# Main_board_Giulia.net
KiCad netlist of a schematic drawn in EAGLE
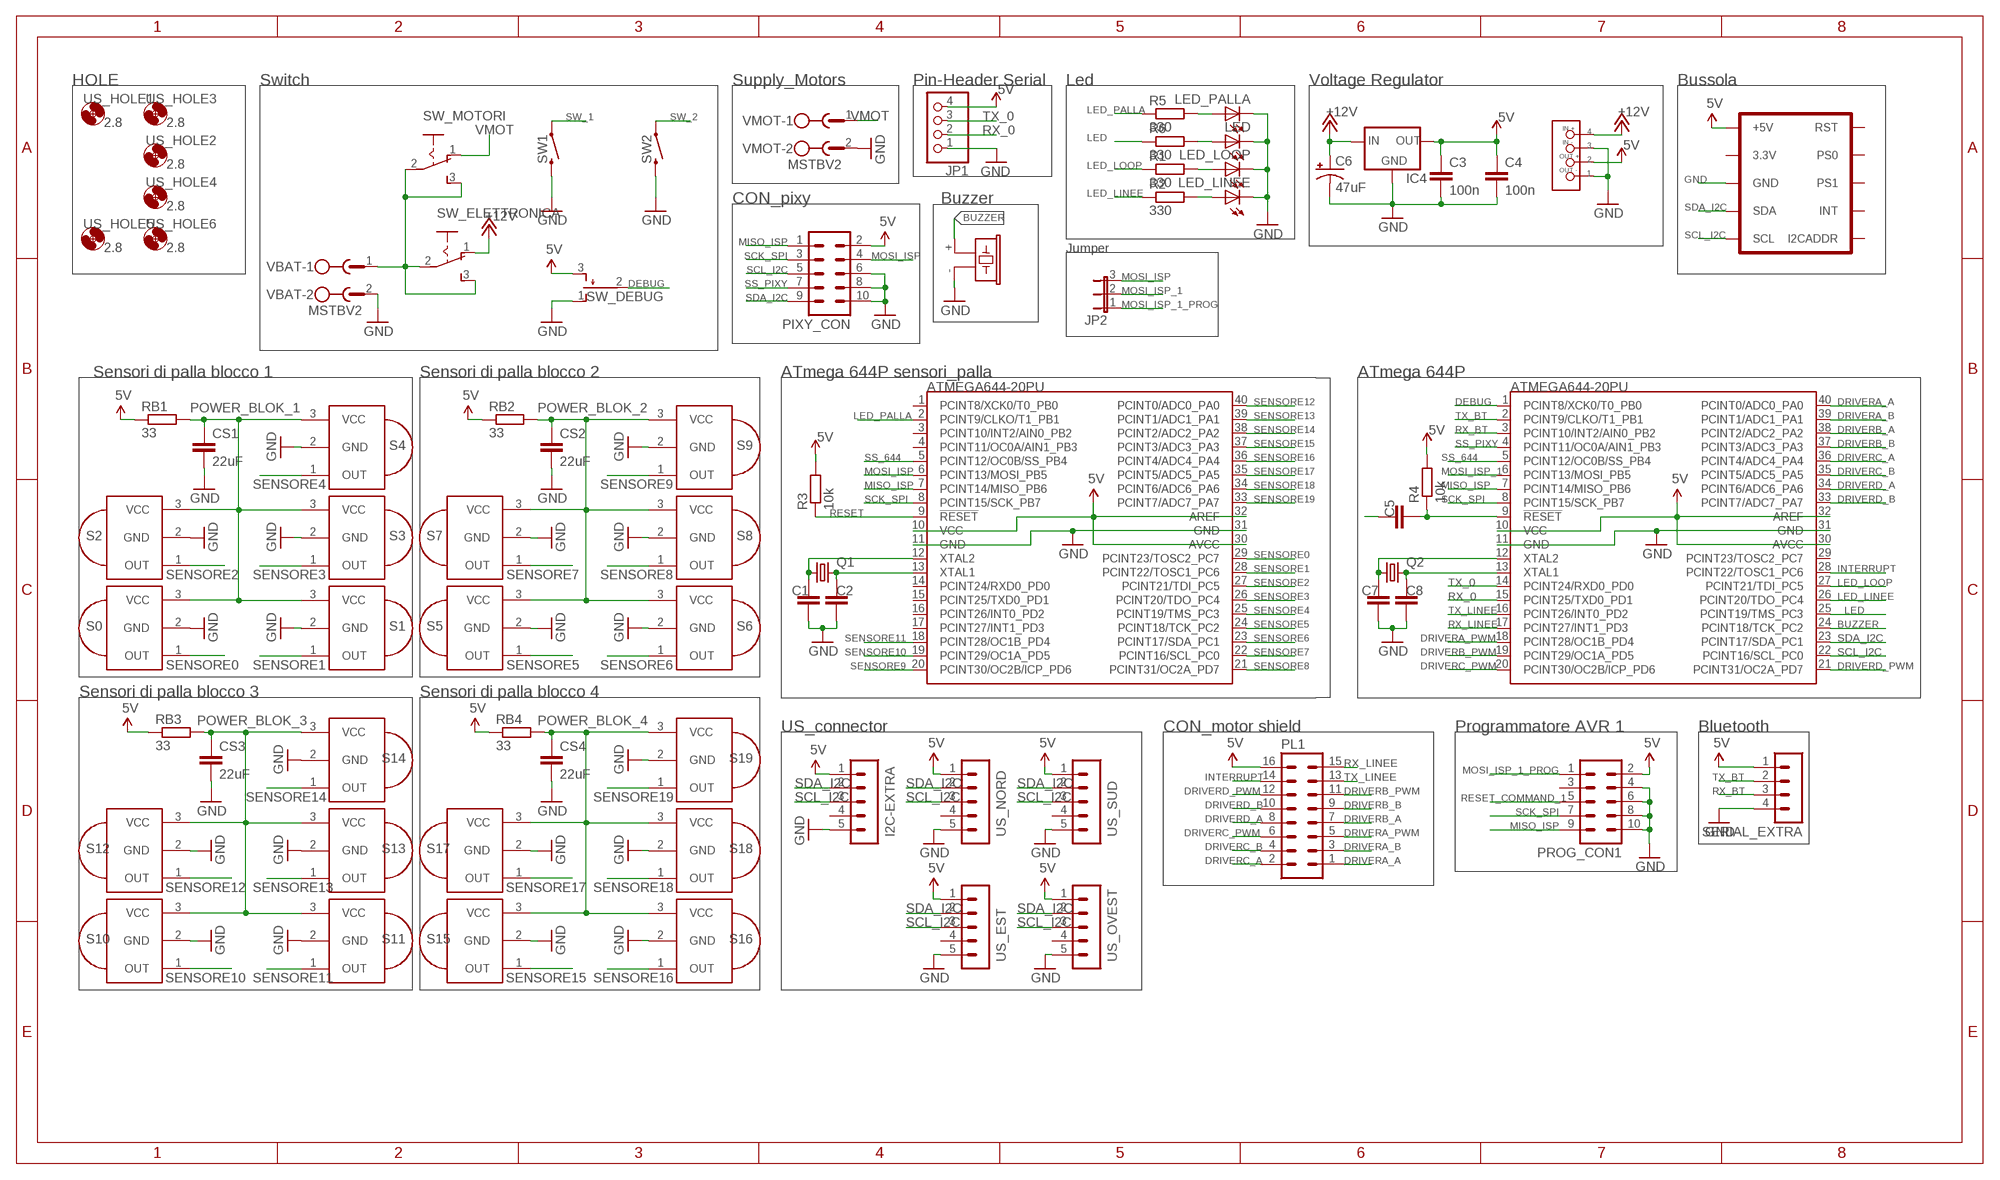
[diagram p0: schematic, sheet 1]

(export (version "E")
  (design (tool "Eeschema 10.0.6"))
  (components
    (comp (ref "C1")
      (value "18p")
      (footprint "eagle-import:C1206")
      (libsource (lib "eagle-import") (part "C-EUC1206"))
    )
    (comp (ref "C2")
      (value "18p")
      (footprint "eagle-import:C1206")
      (libsource (lib "eagle-import") (part "C-EUC1206"))
    )
    (comp (ref "C3")
      (value "100n")
      (footprint "eagle-import:C050-025X075")
      (libsource (lib "eagle-import") (part "C-EU050-025X075"))
    )
    (comp (ref "C4")
      (value "100n")
      (footprint "eagle-import:C050-025X075")
      (libsource (lib "eagle-import") (part "C-EU050-025X075"))
    )
    (comp (ref "C5")
      (value "0.1uF")
      (footprint "eagle-import:C1206")
      (libsource (lib "eagle-import") (part "C-EUC1206"))
    )
    (comp (ref "C6")
      (value "47uF")
      (footprint "eagle-import:CPOL-RADIAL-100UF-25V")
      (libsource (lib "eagle-import") (part "CAP_POLPTH1"))
    )
    (comp (ref "C7")
      (value "18p")
      (footprint "eagle-import:C1206")
      (libsource (lib "eagle-import") (part "C-EUC1206"))
    )
    (comp (ref "C8")
      (value "18p")
      (footprint "eagle-import:C1206")
      (libsource (lib "eagle-import") (part "C-EUC1206"))
    )
    (comp (ref "CS1")
      (value "22uF")
      (footprint "eagle-import:C1206")
      (libsource (lib "eagle-import") (part "C-EUC1206"))
    )
    (comp (ref "CS2")
      (value "22uF")
      (footprint "eagle-import:C1206")
      (libsource (lib "eagle-import") (part "C-EUC1206"))
    )
    (comp (ref "CS3")
      (value "22uF")
      (footprint "eagle-import:C1206")
      (libsource (lib "eagle-import") (part "C-EUC1206"))
    )
    (comp (ref "CS4")
      (value "22uF")
      (footprint "eagle-import:C1206")
      (libsource (lib "eagle-import") (part "C-EUC1206"))
    )
    (comp (ref "I2C-EXTRA")
      (value "MA05-1")
      (footprint "eagle-import:MA05-1")
      (libsource (lib "eagle-import") (part "MA05-1"))
    )
    (comp (ref "IC2")
      (value "ATMEGA644-20PU")
      (footprint "eagle-import:DIL40")
      (libsource (lib "eagle-import") (part "ATMEGA644-PU20"))
    )
    (comp (ref "IC3")
      (value "ATMEGA644-20PU")
      (footprint "eagle-import:DIL40")
      (libsource (lib "eagle-import") (part "ATMEGA644-PU20"))
    )
    (comp (ref "IC4")
      (value "V_REG_78XXSIDE")
      (footprint "eagle-import:78XXL")
      (libsource (lib "eagle-import") (part "V_REG_78XXSIDE"))
    )
    (comp (ref "JP1")
      (value "PINHD-1X4")
      (footprint "eagle-import:1X04")
      (libsource (lib "eagle-import") (part "PINHD-1X4"))
    )
    (comp (ref "JP2")
      (value "JP2E")
      (footprint "eagle-import:JP2")
      (libsource (lib "eagle-import") (part "JP2E"))
    )
    (comp (ref "LED")
      (value "LED3MM")
      (footprint "eagle-import:LED3MM")
      (libsource (lib "eagle-import") (part "LED3MM"))
    )
    (comp (ref "LED_LINEE")
      (value "LED3MM")
      (footprint "eagle-import:LED3MM")
      (libsource (lib "eagle-import") (part "LED3MM"))
    )
    (comp (ref "LED_LOOP")
      (value "LED3MM")
      (footprint "eagle-import:LED3MM")
      (libsource (lib "eagle-import") (part "LED3MM"))
    )
    (comp (ref "LED_PALLA")
      (value "LED3MM")
      (footprint "eagle-import:LED3MM")
      (libsource (lib "eagle-import") (part "LED3MM"))
    )
    (comp (ref "PIXY_CON")
      (value "10V")
      (footprint "eagle-import:10V")
      (libsource (lib "eagle-import") (part "10V"))
    )
    (comp (ref "PL1")
      (value "16V")
      (footprint "eagle-import:16V")
      (libsource (lib "eagle-import") (part "16V"))
    )
    (comp (ref "PROG_CON1")
      (value "10V")
      (footprint "eagle-import:10V")
      (libsource (lib "eagle-import") (part "10V"))
    )
    (comp (ref "Q1")
      (value "CRYSTALHC49UV")
      (footprint "eagle-import:HC49U-V")
      (libsource (lib "eagle-import") (part "CRYSTALHC49UV"))
    )
    (comp (ref "Q2")
      (value "CRYSTALHC49UV")
      (footprint "eagle-import:HC49U-V")
      (libsource (lib "eagle-import") (part "CRYSTALHC49UV"))
    )
    (comp (ref "R1")
      (value "330")
      (footprint "eagle-import:M1206")
      (libsource (lib "eagle-import") (part "R-EU_M1206"))
    )
    (comp (ref "R2")
      (value "330")
      (footprint "eagle-import:M1206")
      (libsource (lib "eagle-import") (part "R-EU_M1206"))
    )
    (comp (ref "R3")
      (value "10k")
      (footprint "eagle-import:M1206")
      (libsource (lib "eagle-import") (part "R-EU_M1206"))
    )
    (comp (ref "R4")
      (value "10k")
      (footprint "eagle-import:M1206")
      (libsource (lib "eagle-import") (part "R-EU_M1206"))
    )
    (comp (ref "R5")
      (value "330")
      (footprint "eagle-import:M1206")
      (libsource (lib "eagle-import") (part "R-EU_M1206"))
    )
    (comp (ref "R6")
      (value "330")
      (footprint "eagle-import:M1206")
      (libsource (lib "eagle-import") (part "R-EU_M1206"))
    )
    (comp (ref "RB1")
      (value "33")
      (footprint "eagle-import:0207_10")
      (libsource (lib "eagle-import") (part "R-EU_0207/10"))
    )
    (comp (ref "RB2")
      (value "33")
      (footprint "eagle-import:0207_10")
      (libsource (lib "eagle-import") (part "R-EU_0207/10"))
    )
    (comp (ref "RB3")
      (value "33")
      (footprint "eagle-import:0207_10")
      (libsource (lib "eagle-import") (part "R-EU_0207/10"))
    )
    (comp (ref "RB4")
      (value "33")
      (footprint "eagle-import:0207_10")
      (libsource (lib "eagle-import") (part "R-EU_0207/10"))
    )
    (comp (ref "S0")
      (value "PNA460XM")
      (footprint "eagle-import:PNA460XM")
      (libsource (lib "eagle-import") (part "PNA460XM"))
    )
    (comp (ref "S1")
      (value "PNA460XM")
      (footprint "eagle-import:PNA460XM")
      (libsource (lib "eagle-import") (part "PNA460XM"))
    )
    (comp (ref "S2")
      (value "PNA460XM")
      (footprint "eagle-import:PNA460XM")
      (libsource (lib "eagle-import") (part "PNA460XM"))
    )
    (comp (ref "S3")
      (value "PNA460XM")
      (footprint "eagle-import:PNA460XM")
      (libsource (lib "eagle-import") (part "PNA460XM"))
    )
    (comp (ref "S4")
      (value "PNA460XM")
      (footprint "eagle-import:PNA460XM")
      (libsource (lib "eagle-import") (part "PNA460XM"))
    )
    (comp (ref "S5")
      (value "PNA460XM")
      (footprint "eagle-import:PNA460XM")
      (libsource (lib "eagle-import") (part "PNA460XM"))
    )
    (comp (ref "S6")
      (value "PNA460XM")
      (footprint "eagle-import:PNA460XM")
      (libsource (lib "eagle-import") (part "PNA460XM"))
    )
    (comp (ref "S7")
      (value "PNA460XM")
      (footprint "eagle-import:PNA460XM")
      (libsource (lib "eagle-import") (part "PNA460XM"))
    )
    (comp (ref "S8")
      (value "PNA460XM")
      (footprint "eagle-import:PNA460XM")
      (libsource (lib "eagle-import") (part "PNA460XM"))
    )
    (comp (ref "S9")
      (value "PNA460XM")
      (footprint "eagle-import:PNA460XM")
      (libsource (lib "eagle-import") (part "PNA460XM"))
    )
    (comp (ref "S10")
      (value "PNA460XM")
      (footprint "eagle-import:PNA460XM")
      (libsource (lib "eagle-import") (part "PNA460XM"))
    )
    (comp (ref "S11")
      (value "PNA460XM")
      (footprint "eagle-import:PNA460XM")
      (libsource (lib "eagle-import") (part "PNA460XM"))
    )
    (comp (ref "S12")
      (value "PNA460XM")
      (footprint "eagle-import:PNA460XM")
      (libsource (lib "eagle-import") (part "PNA460XM"))
    )
    (comp (ref "S13")
      (value "PNA460XM")
      (footprint "eagle-import:PNA460XM")
      (libsource (lib "eagle-import") (part "PNA460XM"))
    )
    (comp (ref "S14")
      (value "PNA460XM")
      (footprint "eagle-import:PNA460XM")
      (libsource (lib "eagle-import") (part "PNA460XM"))
    )
    (comp (ref "S15")
      (value "PNA460XM")
      (footprint "eagle-import:PNA460XM")
      (libsource (lib "eagle-import") (part "PNA460XM"))
    )
    (comp (ref "S16")
      (value "PNA460XM")
      (footprint "eagle-import:PNA460XM")
      (libsource (lib "eagle-import") (part "PNA460XM"))
    )
    (comp (ref "S17")
      (value "PNA460XM")
      (footprint "eagle-import:PNA460XM")
      (libsource (lib "eagle-import") (part "PNA460XM"))
    )
    (comp (ref "S18")
      (value "PNA460XM")
      (footprint "eagle-import:PNA460XM")
      (libsource (lib "eagle-import") (part "PNA460XM"))
    )
    (comp (ref "S19")
      (value "PNA460XM")
      (footprint "eagle-import:PNA460XM")
      (libsource (lib "eagle-import") (part "PNA460XM"))
    )
    (comp (ref "SERIAL_EXTRA")
      (value "MA04-1")
      (footprint "eagle-import:MA04-1")
      (libsource (lib "eagle-import") (part "MA04-1"))
    )
    (comp (ref "SG1")
      (value "F/CM12P")
      (footprint "eagle-import:F_CM12P")
      (libsource (lib "eagle-import") (part "F/CM12P"))
    )
    (comp (ref "SW1")
      (value "SWITCH-MOMENTARY-2")
      (footprint "eagle-import:SWITCH_EVQ2")
      (libsource (lib "eagle-import") (part "SWITCH-MOMENTARY-2"))
    )
    (comp (ref "SW2")
      (value "SWITCH-MOMENTARY-2")
      (footprint "eagle-import:SWITCH_EVQ2")
      (libsource (lib "eagle-import") (part "SWITCH-MOMENTARY-2"))
    )
    (comp (ref "SW_DEBUG")
      (value "TL38PO")
      (footprint "eagle-import:TL3XPO")
      (libsource (lib "eagle-import") (part "TL38PO"))
    )
    (comp (ref "SW_ELETTRONICA")
      (value "255SB")
      (footprint "eagle-import:255SB")
      (libsource (lib "eagle-import") (part "255SB"))
    )
    (comp (ref "SW_MOTORI")
      (value "255SB")
      (footprint "eagle-import:255SB")
      (libsource (lib "eagle-import") (part "255SB"))
    )
    (comp (ref "U$1")
      (value "MINI3ADCDCLM2596")
      (footprint "eagle-import:MINI3ADCDCLM2595")
      (libsource (lib "eagle-import") (part "MINI3ADCDCLM2596"))
    )
    (comp (ref "U$17")
      (value "BNO055")
      (footprint "eagle-import:BNO055")
      (libsource (lib "eagle-import") (part "BNO055"))
    )
    (comp (ref "US_EST")
      (value "MA05-1")
      (footprint "eagle-import:MA05-1")
      (libsource (lib "eagle-import") (part "MA05-1"))
    )
    (comp (ref "US_HOLE1")
      (value "2.8")
      (footprint "eagle-import:2,8")
      (libsource (lib "eagle-import") (part "MOUNT-HOLE2.8"))
    )
    (comp (ref "US_HOLE2")
      (value "2.8")
      (footprint "eagle-import:2,8")
      (libsource (lib "eagle-import") (part "MOUNT-HOLE2.8"))
    )
    (comp (ref "US_HOLE3")
      (value "2.8")
      (footprint "eagle-import:2,8")
      (libsource (lib "eagle-import") (part "MOUNT-HOLE2.8"))
    )
    (comp (ref "US_HOLE4")
      (value "2.8")
      (footprint "eagle-import:2,8")
      (libsource (lib "eagle-import") (part "MOUNT-HOLE2.8"))
    )
    (comp (ref "US_HOLE5")
      (value "2.8")
      (footprint "eagle-import:2,8")
      (libsource (lib "eagle-import") (part "MOUNT-HOLE2.8"))
    )
    (comp (ref "US_HOLE6")
      (value "2.8")
      (footprint "eagle-import:2,8")
      (libsource (lib "eagle-import") (part "MOUNT-HOLE2.8"))
    )
    (comp (ref "US_NORD")
      (value "MA05-1")
      (footprint "eagle-import:MA05-1")
      (libsource (lib "eagle-import") (part "MA05-1"))
    )
    (comp (ref "US_OVEST")
      (value "MA05-1")
      (footprint "eagle-import:MA05-1")
      (libsource (lib "eagle-import") (part "MA05-1"))
    )
    (comp (ref "US_SUD")
      (value "MA05-1")
      (footprint "eagle-import:MA05-1")
      (libsource (lib "eagle-import") (part "MA05-1"))
    )
    (comp (ref "VBAT")
      (value "MSTBV2")
      (footprint "eagle-import:MSTBV2")
      (fields (field (name "MPN") "MSTBV 2,5/2-GF-5.08"))
      (libsource (lib "eagle-import") (part "MSTBV2"))
    )
    (comp (ref "VMOT")
      (value "MSTBV2")
      (footprint "eagle-import:MSTBV2")
      (fields (field (name "MPN") "MSTBV 2,5/2-GF-5.08"))
      (libsource (lib "eagle-import") (part "MSTBV2"))
    )
  )
  (nets
    (net (code "1") (name "+12V") (class "Default")
      (node (ref "C6") (pin "1") (pinfunction "+_1") (pintype "passive"))
      (node (ref "IC4") (pin "IN") (pinfunction "IN_IN") (pintype "input"))
      (node (ref "SW_ELETTRONICA") (pin "1") (pinfunction "O_1") (pintype "passive"))
      (node (ref "U$1") (pin "P$2") (pinfunction "IN1_P$2") (pintype "input"))
      (node (ref "U$1") (pin "P$7") (pinfunction "IN1_P$7") (pintype "input"))
    )
    (net (code "2") (name "/DEBUG") (class "Default")
      (node (ref "IC3") (pin "1") (pinfunction "PCINT8/XCK0/T0_PB0_1") (pintype "bidirectional"))
      (node (ref "SW_DEBUG") (pin "2") (pinfunction "P_2") (pintype "passive"))
    )
    (net (code "3") (name "/DRIVERA_A") (class "Default")
      (node (ref "IC3") (pin "40") (pinfunction "PCINT0/ADC0_PA0_40") (pintype "bidirectional"))
      (node (ref "PL1") (pin "1") (pinfunction "1_1") (pintype "passive"))
    )
    (net (code "4") (name "/DRIVERA_B") (class "Default")
      (node (ref "IC3") (pin "39") (pinfunction "PCINT1/ADC1_PA1_39") (pintype "bidirectional"))
      (node (ref "PL1") (pin "3") (pinfunction "3_3") (pintype "passive"))
    )
    (net (code "5") (name "/DRIVERA_PWM") (class "Default")
      (node (ref "IC3") (pin "18") (pinfunction "PCINT28/OC1B_PD4_18") (pintype "bidirectional"))
      (node (ref "PL1") (pin "5") (pinfunction "5_5") (pintype "passive"))
    )
    (net (code "6") (name "/DRIVERB_A") (class "Default")
      (node (ref "IC3") (pin "38") (pinfunction "PCINT2/ADC2_PA2_38") (pintype "bidirectional"))
      (node (ref "PL1") (pin "7") (pinfunction "7_7") (pintype "passive"))
    )
    (net (code "7") (name "/DRIVERB_B") (class "Default")
      (node (ref "IC3") (pin "37") (pinfunction "PCINT3/ADC3_PA3_37") (pintype "bidirectional"))
      (node (ref "PL1") (pin "9") (pinfunction "9_9") (pintype "passive"))
    )
    (net (code "8") (name "/DRIVERB_PWM") (class "Default")
      (node (ref "IC3") (pin "19") (pinfunction "PCINT29/OC1A_PD5_19") (pintype "bidirectional"))
      (node (ref "PL1") (pin "11") (pinfunction "11_11") (pintype "passive"))
    )
    (net (code "9") (name "/DRIVERC_A") (class "Default")
      (node (ref "IC3") (pin "36") (pinfunction "PCINT4/ADC4_PA4_36") (pintype "bidirectional"))
      (node (ref "PL1") (pin "2") (pinfunction "2_2") (pintype "passive"))
    )
    (net (code "10") (name "/DRIVERC_B") (class "Default")
      (node (ref "IC3") (pin "35") (pinfunction "PCINT5/ADC5_PA5_35") (pintype "bidirectional"))
      (node (ref "PL1") (pin "4") (pinfunction "4_4") (pintype "passive"))
    )
    (net (code "11") (name "/DRIVERC_PWM") (class "Default")
      (node (ref "IC3") (pin "20") (pinfunction "PCINT30/OC2B/ICP_PD6_20") (pintype "bidirectional"))
      (node (ref "PL1") (pin "6") (pinfunction "6_6") (pintype "passive"))
    )
    (net (code "12") (name "/DRIVERD_A") (class "Default")
      (node (ref "IC3") (pin "34") (pinfunction "PCINT6/ADC6_PA6_34") (pintype "bidirectional"))
      (node (ref "PL1") (pin "8") (pinfunction "8_8") (pintype "passive"))
    )
    (net (code "13") (name "/DRIVERD_B") (class "Default")
      (node (ref "IC3") (pin "33") (pinfunction "PCINT7/ADC7_PA7_33") (pintype "bidirectional"))
      (node (ref "PL1") (pin "10") (pinfunction "10_10") (pintype "passive"))
    )
    (net (code "14") (name "/DRIVERD_PWM") (class "Default")
      (node (ref "IC3") (pin "21") (pinfunction "PCINT31/OC2A_PD7_21") (pintype "bidirectional"))
      (node (ref "PL1") (pin "12") (pinfunction "12_12") (pintype "passive"))
    )
    (net (code "15") (name "/INTERRUPT") (class "Default")
      (node (ref "IC3") (pin "28") (pinfunction "PCINT22/TOSC1_PC6_28") (pintype "bidirectional"))
      (node (ref "PL1") (pin "14") (pinfunction "14_14") (pintype "passive"))
    )
    (net (code "16") (name "/LED") (class "Default")
      (node (ref "IC3") (pin "25") (pinfunction "PCINT19/TMS_PC3_25") (pintype "bidirectional"))
      (node (ref "R6") (pin "1") (pinfunction "1_1") (pintype "passive"))
    )
    (net (code "17") (name "/LED_LINEE") (class "Default")
      (node (ref "IC3") (pin "26") (pinfunction "PCINT20/TDO_PC4_26") (pintype "bidirectional"))
      (node (ref "R2") (pin "1") (pinfunction "1_1") (pintype "passive"))
    )
    (net (code "18") (name "/LED_LOOP") (class "Default")
      (node (ref "IC3") (pin "27") (pinfunction "PCINT21/TDI_PC5_27") (pintype "bidirectional"))
      (node (ref "R1") (pin "1") (pinfunction "1_1") (pintype "passive"))
    )
    (net (code "19") (name "/LED_PALLA") (class "Default")
      (node (ref "IC2") (pin "2") (pinfunction "PCINT9/CLKO/T1_PB1_2") (pintype "bidirectional"))
      (node (ref "R5") (pin "1") (pinfunction "1_1") (pintype "passive"))
    )
    (net (code "20") (name "/MISO_ISP") (class "Default")
      (node (ref "IC2") (pin "7") (pinfunction "PCINT14/MISO_PB6_7") (pintype "bidirectional"))
      (node (ref "IC3") (pin "7") (pinfunction "PCINT14/MISO_PB6_7") (pintype "bidirectional"))
      (node (ref "PIXY_CON") (pin "1") (pinfunction "1_1") (pintype "passive"))
      (node (ref "PROG_CON1") (pin "9") (pinfunction "9_9") (pintype "passive"))
    )
    (net (code "21") (name "/MOSI_ISP") (class "Default")
      (node (ref "IC2") (pin "6") (pinfunction "PCINT13/MOSI_PB5_6") (pintype "bidirectional"))
      (node (ref "JP2") (pin "3") (pinfunction "3_3") (pintype "passive"))
      (node (ref "PIXY_CON") (pin "4") (pinfunction "4_4") (pintype "passive"))
    )
    (net (code "22") (name "/MOSI_ISP_1") (class "Default")
      (node (ref "IC3") (pin "6") (pinfunction "PCINT13/MOSI_PB5_6") (pintype "bidirectional"))
      (node (ref "JP2") (pin "2") (pinfunction "2_2") (pintype "passive"))
    )
    (net (code "23") (name "/MOSI_ISP_1_PROG") (class "Default")
      (node (ref "JP2") (pin "1") (pinfunction "1_1") (pintype "passive"))
      (node (ref "PROG_CON1") (pin "1") (pinfunction "1_1") (pintype "passive"))
    )
    (net (code "24") (name "/POWER_BLOK_1") (class "Default")
      (node (ref "CS1") (pin "1") (pinfunction "1_1") (pintype "passive"))
      (node (ref "RB1") (pin "2") (pinfunction "2_2") (pintype "passive"))
      (node (ref "S0") (pin "3") (pinfunction "VCC_3") (pintype "power_in"))
      (node (ref "S1") (pin "3") (pinfunction "VCC_3") (pintype "power_in"))
      (node (ref "S2") (pin "3") (pinfunction "VCC_3") (pintype "power_in"))
      (node (ref "S3") (pin "3") (pinfunction "VCC_3") (pintype "power_in"))
      (node (ref "S4") (pin "3") (pinfunction "VCC_3") (pintype "power_in"))
    )
    (net (code "25") (name "/POWER_BLOK_2") (class "Default")
      (node (ref "CS2") (pin "1") (pinfunction "1_1") (pintype "passive"))
      (node (ref "RB2") (pin "2") (pinfunction "2_2") (pintype "passive"))
      (node (ref "S5") (pin "3") (pinfunction "VCC_3") (pintype "power_in"))
      (node (ref "S6") (pin "3") (pinfunction "VCC_3") (pintype "power_in"))
      (node (ref "S7") (pin "3") (pinfunction "VCC_3") (pintype "power_in"))
      (node (ref "S8") (pin "3") (pinfunction "VCC_3") (pintype "power_in"))
      (node (ref "S9") (pin "3") (pinfunction "VCC_3") (pintype "power_in"))
    )
    (net (code "26") (name "/POWER_BLOK_3") (class "Default")
      (node (ref "CS3") (pin "1") (pinfunction "1_1") (pintype "passive"))
      (node (ref "RB3") (pin "2") (pinfunction "2_2") (pintype "passive"))
      (node (ref "S10") (pin "3") (pinfunction "VCC_3") (pintype "power_in"))
      (node (ref "S11") (pin "3") (pinfunction "VCC_3") (pintype "power_in"))
      (node (ref "S12") (pin "3") (pinfunction "VCC_3") (pintype "power_in"))
      (node (ref "S13") (pin "3") (pinfunction "VCC_3") (pintype "power_in"))
      (node (ref "S14") (pin "3") (pinfunction "VCC_3") (pintype "power_in"))
    )
    (net (code "27") (name "/POWER_BLOK_4") (class "Default")
      (node (ref "CS4") (pin "1") (pinfunction "1_1") (pintype "passive"))
      (node (ref "RB4") (pin "2") (pinfunction "2_2") (pintype "passive"))
      (node (ref "S15") (pin "3") (pinfunction "VCC_3") (pintype "power_in"))
      (node (ref "S16") (pin "3") (pinfunction "VCC_3") (pintype "power_in"))
      (node (ref "S17") (pin "3") (pinfunction "VCC_3") (pintype "power_in"))
      (node (ref "S18") (pin "3") (pinfunction "VCC_3") (pintype "power_in"))
      (node (ref "S19") (pin "3") (pinfunction "VCC_3") (pintype "power_in"))
    )
    (net (code "28") (name "/RESET") (class "Default")
      (node (ref "IC2") (pin "9") (pinfunction "~{RESET}_9") (pintype "input"))
      (node (ref "R3") (pin "1") (pinfunction "1_1") (pintype "passive"))
    )
    (net (code "29") (name "/RESET_COMMAND_1") (class "Default")
      (node (ref "C5") (pin "1") (pinfunction "1_1") (pintype "passive"))
      (node (ref "PROG_CON1") (pin "5") (pinfunction "5_5") (pintype "passive"))
    )
    (net (code "30") (name "/RX_0") (class "Default")
      (node (ref "IC3") (pin "15") (pinfunction "PCINT25/TXD0_PD1_15") (pintype "bidirectional"))
      (node (ref "JP1") (pin "2") (pinfunction "2_2") (pintype "passive"))
    )
    (net (code "31") (name "/RX_BT") (class "Default")
      (node (ref "IC3") (pin "3") (pinfunction "PCINT10/INT2/AIN0_PB2_3") (pintype "bidirectional"))
      (node (ref "SERIAL_EXTRA") (pin "3") (pinfunction "3_3") (pintype "passive"))
    )
    (net (code "32") (name "/RX_LINEE") (class "Default")
      (node (ref "IC3") (pin "17") (pinfunction "PCINT27/INT1_PD3_17") (pintype "bidirectional"))
      (node (ref "PL1") (pin "15") (pinfunction "15_15") (pintype "passive"))
    )
    (net (code "33") (name "/SCK_SPI") (class "Default")
      (node (ref "IC2") (pin "8") (pinfunction "PCINT15/SCK_PB7_8") (pintype "bidirectional"))
      (node (ref "IC3") (pin "8") (pinfunction "PCINT15/SCK_PB7_8") (pintype "bidirectional"))
      (node (ref "PIXY_CON") (pin "3") (pinfunction "3_3") (pintype "passive"))
      (node (ref "PROG_CON1") (pin "7") (pinfunction "7_7") (pintype "passive"))
    )
    (net (code "34") (name "/SCL_I2C") (class "Default")
      (node (ref "I2C-EXTRA") (pin "3") (pinfunction "3_3") (pintype "passive"))
      (node (ref "IC3") (pin "22") (pinfunction "PCINT16/SCL_PC0_22") (pintype "bidirectional"))
      (node (ref "PIXY_CON") (pin "5") (pinfunction "5_5") (pintype "passive"))
      (node (ref "U$17") (pin "SCL") (pinfunction "SCL_SCL") (pintype "bidirectional"))
      (node (ref "US_EST") (pin "3") (pinfunction "3_3") (pintype "passive"))
      (node (ref "US_NORD") (pin "3") (pinfunction "3_3") (pintype "passive"))
      (node (ref "US_OVEST") (pin "3") (pinfunction "3_3") (pintype "passive"))
      (node (ref "US_SUD") (pin "3") (pinfunction "3_3") (pintype "passive"))
    )
    (net (code "35") (name "/SDA_I2C") (class "Default")
      (node (ref "I2C-EXTRA") (pin "2") (pinfunction "2_2") (pintype "passive"))
      (node (ref "IC3") (pin "23") (pinfunction "PCINT17/SDA_PC1_23") (pintype "bidirectional"))
      (node (ref "PIXY_CON") (pin "9") (pinfunction "9_9") (pintype "passive"))
      (node (ref "U$17") (pin "SDA") (pinfunction "SDA_SDA") (pintype "bidirectional"))
      (node (ref "US_EST") (pin "2") (pinfunction "2_2") (pintype "passive"))
      (node (ref "US_NORD") (pin "2") (pinfunction "2_2") (pintype "passive"))
      (node (ref "US_OVEST") (pin "2") (pinfunction "2_2") (pintype "passive"))
      (node (ref "US_SUD") (pin "2") (pinfunction "2_2") (pintype "passive"))
    )
    (net (code "36") (name "/SENSORE0") (class "Default")
      (node (ref "IC2") (pin "29") (pinfunction "PCINT23/TOSC2_PC7_29") (pintype "bidirectional"))
      (node (ref "S0") (pin "1") (pinfunction "OUT_1") (pintype "output"))
    )
    (net (code "37") (name "/SENSORE1") (class "Default")
      (node (ref "IC2") (pin "28") (pinfunction "PCINT22/TOSC1_PC6_28") (pintype "bidirectional"))
      (node (ref "S1") (pin "1") (pinfunction "OUT_1") (pintype "output"))
    )
    (net (code "38") (name "/SENSORE2") (class "Default")
      (node (ref "IC2") (pin "27") (pinfunction "PCINT21/TDI_PC5_27") (pintype "bidirectional"))
      (node (ref "S2") (pin "1") (pinfunction "OUT_1") (pintype "output"))
    )
    (net (code "39") (name "/SENSORE3") (class "Default")
      (node (ref "IC2") (pin "26") (pinfunction "PCINT20/TDO_PC4_26") (pintype "bidirectional"))
      (node (ref "S3") (pin "1") (pinfunction "OUT_1") (pintype "output"))
    )
    (net (code "40") (name "/SENSORE4") (class "Default")
      (node (ref "IC2") (pin "25") (pinfunction "PCINT19/TMS_PC3_25") (pintype "bidirectional"))
      (node (ref "S4") (pin "1") (pinfunction "OUT_1") (pintype "output"))
    )
    (net (code "41") (name "/SENSORE5") (class "Default")
      (node (ref "IC2") (pin "24") (pinfunction "PCINT18/TCK_PC2_24") (pintype "bidirectional"))
      (node (ref "S5") (pin "1") (pinfunction "OUT_1") (pintype "output"))
    )
    (net (code "42") (name "/SENSORE6") (class "Default")
      (node (ref "IC2") (pin "23") (pinfunction "PCINT17/SDA_PC1_23") (pintype "bidirectional"))
      (node (ref "S6") (pin "1") (pinfunction "OUT_1") (pintype "output"))
    )
    (net (code "43") (name "/SENSORE7") (class "Default")
      (node (ref "IC2") (pin "22") (pinfunction "PCINT16/SCL_PC0_22") (pintype "bidirectional"))
      (node (ref "S7") (pin "1") (pinfunction "OUT_1") (pintype "output"))
    )
    (net (code "44") (name "/SENSORE8") (class "Default")
      (node (ref "IC2") (pin "21") (pinfunction "PCINT31/OC2A_PD7_21") (pintype "bidirectional"))
      (node (ref "S8") (pin "1") (pinfunction "OUT_1") (pintype "output"))
    )
    (net (code "45") (name "/SENSORE9") (class "Default")
      (node (ref "IC2") (pin "20") (pinfunction "PCINT30/OC2B/ICP_PD6_20") (pintype "bidirectional"))
      (node (ref "S9") (pin "1") (pinfunction "OUT_1") (pintype "output"))
    )
    (net (code "46") (name "/SENSORE10") (class "Default")
      (node (ref "IC2") (pin "19") (pinfunction "PCINT29/OC1A_PD5_19") (pintype "bidirectional"))
      (node (ref "S10") (pin "1") (pinfunction "OUT_1") (pintype "output"))
    )
    (net (code "47") (name "/SENSORE11") (class "Default")
      (node (ref "IC2") (pin "18") (pinfunction "PCINT28/OC1B_PD4_18") (pintype "bidirectional"))
      (node (ref "S11") (pin "1") (pinfunction "OUT_1") (pintype "output"))
    )
    (net (code "48") (name "/SENSORE12") (class "Default")
      (node (ref "IC2") (pin "40") (pinfunction "PCINT0/ADC0_PA0_40") (pintype "bidirectional"))
      (node (ref "S12") (pin "1") (pinfunction "OUT_1") (pintype "output"))
    )
    (net (code "49") (name "/SENSORE13") (class "Default")
      (node (ref "IC2") (pin "39") (pinfunction "PCINT1/ADC1_PA1_39") (pintype "bidirectional"))
      (node (ref "S13") (pin "1") (pinfunction "OUT_1") (pintype "output"))
    )
    (net (code "50") (name "/SENSORE14") (class "Default")
      (node (ref "IC2") (pin "38") (pinfunction "PCINT2/ADC2_PA2_38") (pintype "bidirectional"))
      (node (ref "S14") (pin "1") (pinfunction "OUT_1") (pintype "output"))
    )
    (net (code "51") (name "/SENSORE15") (class "Default")
      (node (ref "IC2") (pin "37") (pinfunction "PCINT3/ADC3_PA3_37") (pintype "bidirectional"))
      (node (ref "S15") (pin "1") (pinfunction "OUT_1") (pintype "output"))
    )
    (net (code "52") (name "/SENSORE16") (class "Default")
      (node (ref "IC2") (pin "36") (pinfunction "PCINT4/ADC4_PA4_36") (pintype "bidirectional"))
      (node (ref "S16") (pin "1") (pinfunction "OUT_1") (pintype "output"))
    )
    (net (code "53") (name "/SENSORE17") (class "Default")
      (node (ref "IC2") (pin "35") (pinfunction "PCINT5/ADC5_PA5_35") (pintype "bidirectional"))
      (node (ref "S17") (pin "1") (pinfunction "OUT_1") (pintype "output"))
    )
    (net (code "54") (name "/SENSORE18") (class "Default")
      (node (ref "IC2") (pin "34") (pinfunction "PCINT6/ADC6_PA6_34") (pintype "bidirectional"))
      (node (ref "S18") (pin "1") (pinfunction "OUT_1") (pintype "output"))
    )
    (net (code "55") (name "/SENSORE19") (class "Default")
      (node (ref "IC2") (pin "33") (pinfunction "PCINT7/ADC7_PA7_33") (pintype "bidirectional"))
      (node (ref "S19") (pin "1") (pinfunction "OUT_1") (pintype "output"))
    )
    (net (code "56") (name "/SS_644") (class "Default")
      (node (ref "IC2") (pin "5") (pinfunction "PCINT12/OC0B/SS_PB4_5") (pintype "bidirectional"))
      (node (ref "IC3") (pin "5") (pinfunction "PCINT12/OC0B/SS_PB4_5") (pintype "bidirectional"))
    )
    (net (code "57") (name "/SS_PIXY") (class "Default")
      (node (ref "IC3") (pin "4") (pinfunction "PCINT11/OC0A/AIN1_PB3_4") (pintype "bidirectional"))
      (node (ref "PIXY_CON") (pin "7") (pinfunction "7_7") (pintype "passive"))
    )
    (net (code "58") (name "/SW_1") (class "Default")
      (node (ref "SW1") (pin "P$1") (pinfunction "1_P$1") (pintype "passive"))
    )
    (net (code "59") (name "/SW_2") (class "Default")
      (node (ref "SW2") (pin "P$1") (pinfunction "1_P$1") (pintype "passive"))
    )
    (net (code "60") (name "/TX_0") (class "Default")
      (node (ref "IC3") (pin "14") (pinfunction "PCINT24/RXD0_PD0_14") (pintype "bidirectional"))
      (node (ref "JP1") (pin "3") (pinfunction "3_3") (pintype "passive"))
    )
    (net (code "61") (name "/TX_BT") (class "Default")
      (node (ref "IC3") (pin "2") (pinfunction "PCINT9/CLKO/T1_PB1_2") (pintype "bidirectional"))
      (node (ref "SERIAL_EXTRA") (pin "2") (pinfunction "2_2") (pintype "passive"))
    )
    (net (code "62") (name "/TX_LINEE") (class "Default")
      (node (ref "IC3") (pin "16") (pinfunction "PCINT26/INT0_PD2_16") (pintype "bidirectional"))
      (node (ref "PL1") (pin "13") (pinfunction "13_13") (pintype "passive"))
    )
    (net (code "63") (name "/VMOT") (class "Default")
      (node (ref "SW_MOTORI") (pin "1") (pinfunction "O_1") (pintype "passive"))
      (node (ref "VMOT") (pin "1") (pinfunction "1_1") (pintype "passive"))
    )
    (net (code "64") (name "5V") (class "Default")
      (node (ref "C3") (pin "1") (pinfunction "1_1") (pintype "passive"))
      (node (ref "C4") (pin "1") (pinfunction "1_1") (pintype "passive"))
      (node (ref "I2C-EXTRA") (pin "1") (pinfunction "1_1") (pintype "passive"))
      (node (ref "IC2") (pin "10") (pinfunction "VCC_10") (pintype "power_in"))
      (node (ref "IC2") (pin "30") (pinfunction "AVCC_30") (pintype "power_in"))
      (node (ref "IC2") (pin "32") (pinfunction "AREF_32") (pintype "passive"))
      (node (ref "IC3") (pin "10") (pinfunction "VCC_10") (pintype "power_in"))
      (node (ref "IC3") (pin "30") (pinfunction "AVCC_30") (pintype "power_in"))
      (node (ref "IC3") (pin "32") (pinfunction "AREF_32") (pintype "passive"))
      (node (ref "IC4") (pin "OUT") (pinfunction "OUT_OUT") (pintype "output"))
      (node (ref "JP1") (pin "4") (pinfunction "4_4") (pintype "passive"))
      (node (ref "PIXY_CON") (pin "2") (pinfunction "2_2") (pintype "passive"))
      (node (ref "PL1") (pin "16") (pinfunction "16_16") (pintype "passive"))
      (node (ref "PROG_CON1") (pin "2") (pinfunction "2_2") (pintype "passive"))
      (node (ref "R3") (pin "2") (pinfunction "2_2") (pintype "passive"))
      (node (ref "R4") (pin "2") (pinfunction "2_2") (pintype "passive"))
      (node (ref "RB1") (pin "1") (pinfunction "1_1") (pintype "passive"))
      (node (ref "RB2") (pin "1") (pinfunction "1_1") (pintype "passive"))
      (node (ref "RB3") (pin "1") (pinfunction "1_1") (pintype "passive"))
      (node (ref "RB4") (pin "1") (pinfunction "1_1") (pintype "passive"))
      (node (ref "SERIAL_EXTRA") (pin "1") (pinfunction "1_1") (pintype "passive"))
      (node (ref "SW_DEBUG") (pin "3") (pinfunction "S_3") (pintype "passive"))
      (node (ref "U$1") (pin "P$1") (pinfunction "OUT+_P$1") (pintype "output"))
      (node (ref "U$1") (pin "P$8") (pinfunction "OUT+_P$8") (pintype "output"))
      (node (ref "U$17") (pin "VIN") (pinfunction "+5V_VIN") (pintype "bidirectional"))
      (node (ref "US_EST") (pin "1") (pinfunction "1_1") (pintype "passive"))
      (node (ref "US_NORD") (pin "1") (pinfunction "1_1") (pintype "passive"))
      (node (ref "US_OVEST") (pin "1") (pinfunction "1_1") (pintype "passive"))
      (node (ref "US_SUD") (pin "1") (pinfunction "1_1") (pintype "passive"))
    )
    (net (code "65") (name "BUZZER") (class "Default")
      (node (ref "IC3") (pin "24") (pinfunction "PCINT18/TCK_PC2_24") (pintype "bidirectional"))
      (node (ref "SG1") (pin "+") (pinfunction "1_+") (pintype "passive"))
    )
    (net (code "66") (name "GND") (class "Default")
      (node (ref "C1") (pin "2") (pinfunction "2_2") (pintype "passive"))
      (node (ref "C2") (pin "2") (pinfunction "2_2") (pintype "passive"))
      (node (ref "C3") (pin "2") (pinfunction "2_2") (pintype "passive"))
      (node (ref "C4") (pin "2") (pinfunction "2_2") (pintype "passive"))
      (node (ref "C6") (pin "2") (pinfunction "-_2") (pintype "passive"))
      (node (ref "C7") (pin "2") (pinfunction "2_2") (pintype "passive"))
      (node (ref "C8") (pin "2") (pinfunction "2_2") (pintype "passive"))
      (node (ref "CS1") (pin "2") (pinfunction "2_2") (pintype "passive"))
      (node (ref "CS2") (pin "2") (pinfunction "2_2") (pintype "passive"))
      (node (ref "CS3") (pin "2") (pinfunction "2_2") (pintype "passive"))
      (node (ref "CS4") (pin "2") (pinfunction "2_2") (pintype "passive"))
      (node (ref "I2C-EXTRA") (pin "5") (pinfunction "5_5") (pintype "passive"))
      (node (ref "IC2") (pin "11") (pinfunction "GND_11") (pintype "power_in"))
      (node (ref "IC2") (pin "31") (pinfunction "GND_31") (pintype "power_in"))
      (node (ref "IC3") (pin "11") (pinfunction "GND_11") (pintype "power_in"))
      (node (ref "IC3") (pin "31") (pinfunction "GND_31") (pintype "power_in"))
      (node (ref "IC4") (pin "GND") (pinfunction "GND_GND") (pintype "input"))
      (node (ref "JP1") (pin "1") (pinfunction "1_1") (pintype "passive"))
      (node (ref "LED") (pin "K") (pinfunction "C_K") (pintype "passive"))
      (node (ref "LED_LINEE") (pin "K") (pinfunction "C_K") (pintype "passive"))
      (node (ref "LED_LOOP") (pin "K") (pinfunction "C_K") (pintype "passive"))
      (node (ref "LED_PALLA") (pin "K") (pinfunction "C_K") (pintype "passive"))
      (node (ref "PIXY_CON") (pin "10") (pinfunction "10_10") (pintype "passive"))
      (node (ref "PIXY_CON") (pin "6") (pinfunction "6_6") (pintype "passive"))
      (node (ref "PIXY_CON") (pin "8") (pinfunction "8_8") (pintype "passive"))
      (node (ref "PROG_CON1") (pin "10") (pinfunction "10_10") (pintype "passive"))
      (node (ref "PROG_CON1") (pin "4") (pinfunction "4_4") (pintype "passive"))
      (node (ref "PROG_CON1") (pin "6") (pinfunction "6_6") (pintype "passive"))
      (node (ref "PROG_CON1") (pin "8") (pinfunction "8_8") (pintype "passive"))
      (node (ref "S0") (pin "2") (pinfunction "GND_2") (pintype "power_in"))
      (node (ref "S1") (pin "2") (pinfunction "GND_2") (pintype "power_in"))
      (node (ref "S10") (pin "2") (pinfunction "GND_2") (pintype "power_in"))
      (node (ref "S11") (pin "2") (pinfunction "GND_2") (pintype "power_in"))
      (node (ref "S12") (pin "2") (pinfunction "GND_2") (pintype "power_in"))
      (node (ref "S13") (pin "2") (pinfunction "GND_2") (pintype "power_in"))
      (node (ref "S14") (pin "2") (pinfunction "GND_2") (pintype "power_in"))
      (node (ref "S15") (pin "2") (pinfunction "GND_2") (pintype "power_in"))
      (node (ref "S16") (pin "2") (pinfunction "GND_2") (pintype "power_in"))
      (node (ref "S17") (pin "2") (pinfunction "GND_2") (pintype "power_in"))
      (node (ref "S18") (pin "2") (pinfunction "GND_2") (pintype "power_in"))
      (node (ref "S19") (pin "2") (pinfunction "GND_2") (pintype "power_in"))
      (node (ref "S2") (pin "2") (pinfunction "GND_2") (pintype "power_in"))
      (node (ref "S3") (pin "2") (pinfunction "GND_2") (pintype "power_in"))
      (node (ref "S4") (pin "2") (pinfunction "GND_2") (pintype "power_in"))
      (node (ref "S5") (pin "2") (pinfunction "GND_2") (pintype "power_in"))
      (node (ref "S6") (pin "2") (pinfunction "GND_2") (pintype "power_in"))
      (node (ref "S7") (pin "2") (pinfunction "GND_2") (pintype "power_in"))
      (node (ref "S8") (pin "2") (pinfunction "GND_2") (pintype "power_in"))
      (node (ref "S9") (pin "2") (pinfunction "GND_2") (pintype "power_in"))
      (node (ref "SERIAL_EXTRA") (pin "4") (pinfunction "4_4") (pintype "passive"))
      (node (ref "SG1") (pin "-") (pinfunction "2_-") (pintype "passive"))
      (node (ref "SW1") (pin "P$2") (pinfunction "2_P$2") (pintype "passive"))
      (node (ref "SW2") (pin "P$2") (pinfunction "2_P$2") (pintype "passive"))
      (node (ref "SW_DEBUG") (pin "1") (pinfunction "O_1") (pintype "passive"))
      (node (ref "U$1") (pin "P$3") (pinfunction "IN2_P$3") (pintype "input"))
      (node (ref "U$1") (pin "P$4") (pinfunction "OUT-_P$4") (pintype "output"))
      (node (ref "U$1") (pin "P$5") (pinfunction "IN2_P$5") (pintype "input"))
      (node (ref "U$1") (pin "P$6") (pinfunction "OUT-_P$6") (pintype "output"))
      (node (ref "U$17") (pin "GND") (pinfunction "GND_GND") (pintype "bidirectional"))
      (node (ref "US_EST") (pin "5") (pinfunction "5_5") (pintype "passive"))
      (node (ref "US_NORD") (pin "5") (pinfunction "5_5") (pintype "passive"))
      (node (ref "US_OVEST") (pin "5") (pinfunction "5_5") (pintype "passive"))
      (node (ref "US_SUD") (pin "5") (pinfunction "5_5") (pintype "passive"))
      (node (ref "VBAT") (pin "2") (pinfunction "1_2") (pintype "passive"))
      (node (ref "VMOT") (pin "2") (pinfunction "1_2") (pintype "passive"))
    )
    (net (code "67") (name "Net-(IC2-XTAL1)") (class "Default")
      (node (ref "C2") (pin "1") (pinfunction "1_1") (pintype "passive"))
      (node (ref "IC2") (pin "13") (pinfunction "XTAL1_13") (pintype "input"))
      (node (ref "Q1") (pin "2") (pinfunction "2_2") (pintype "passive"))
    )
    (net (code "68") (name "Net-(IC2-XTAL2)") (class "Default")
      (node (ref "C1") (pin "1") (pinfunction "1_1") (pintype "passive"))
      (node (ref "IC2") (pin "12") (pinfunction "XTAL2_12") (pintype "output"))
      (node (ref "Q1") (pin "1") (pinfunction "1_1") (pintype "passive"))
    )
    (net (code "69") (name "Net-(IC3-XTAL1)") (class "Default")
      (node (ref "C8") (pin "1") (pinfunction "1_1") (pintype "passive"))
      (node (ref "IC3") (pin "13") (pinfunction "XTAL1_13") (pintype "input"))
      (node (ref "Q2") (pin "2") (pinfunction "2_2") (pintype "passive"))
    )
    (net (code "70") (name "Net-(IC3-XTAL2)") (class "Default")
      (node (ref "C7") (pin "1") (pinfunction "1_1") (pintype "passive"))
      (node (ref "IC3") (pin "12") (pinfunction "XTAL2_12") (pintype "output"))
      (node (ref "Q2") (pin "1") (pinfunction "1_1") (pintype "passive"))
    )
    (net (code "71") (name "Net-(IC3-~{RESET})") (class "Default")
      (node (ref "C5") (pin "2") (pinfunction "2_2") (pintype "passive"))
      (node (ref "IC3") (pin "9") (pinfunction "~{RESET}_9") (pintype "input"))
      (node (ref "R4") (pin "1") (pinfunction "1_1") (pintype "passive"))
    )
    (net (code "72") (name "Net-(LED-PadA)") (class "Default")
      (node (ref "LED") (pin "A") (pinfunction "A_A") (pintype "passive"))
      (node (ref "R6") (pin "2") (pinfunction "2_2") (pintype "passive"))
    )
    (net (code "73") (name "Net-(LED_LINEE-PadA)") (class "Default")
      (node (ref "LED_LINEE") (pin "A") (pinfunction "A_A") (pintype "passive"))
      (node (ref "R2") (pin "2") (pinfunction "2_2") (pintype "passive"))
    )
    (net (code "74") (name "Net-(LED_LOOP-PadA)") (class "Default")
      (node (ref "LED_LOOP") (pin "A") (pinfunction "A_A") (pintype "passive"))
      (node (ref "R1") (pin "2") (pinfunction "2_2") (pintype "passive"))
    )
    (net (code "75") (name "Net-(LED_PALLA-PadA)") (class "Default")
      (node (ref "LED_PALLA") (pin "A") (pinfunction "A_A") (pintype "passive"))
      (node (ref "R5") (pin "2") (pinfunction "2_2") (pintype "passive"))
    )
    (net (code "76") (name "Net-(SW_ELETTRONICA-P)") (class "Default")
      (node (ref "SW_ELETTRONICA") (pin "2") (pinfunction "P_2") (pintype "passive"))
      (node (ref "SW_ELETTRONICA") (pin "3") (pinfunction "S_3") (pintype "passive"))
      (node (ref "SW_MOTORI") (pin "2") (pinfunction "P_2") (pintype "passive"))
      (node (ref "SW_MOTORI") (pin "3") (pinfunction "S_3") (pintype "passive"))
      (node (ref "VBAT") (pin "1") (pinfunction "1_1") (pintype "passive"))
    )
    (net (code "77") (name "unconnected-(I2C-EXTRA-Pad4)") (class "Default")
      (node (ref "I2C-EXTRA") (pin "4") (pinfunction "4_4") (pintype "passive"))
    )
    (net (code "78") (name "unconnected-(IC2-PCINT8{slash}XCK0{slash}T0_PB0-Pad1)") (class "Default")
      (node (ref "IC2") (pin "1") (pinfunction "PCINT8/XCK0/T0_PB0_1") (pintype "bidirectional"))
    )
    (net (code "79") (name "unconnected-(IC2-PCINT10{slash}INT2{slash}AIN0_PB2-Pad3)") (class "Default")
      (node (ref "IC2") (pin "3") (pinfunction "PCINT10/INT2/AIN0_PB2_3") (pintype "bidirectional"))
    )
    (net (code "80") (name "unconnected-(IC2-PCINT11{slash}OC0A{slash}AIN1_PB3-Pad4)") (class "Default")
      (node (ref "IC2") (pin "4") (pinfunction "PCINT11/OC0A/AIN1_PB3_4") (pintype "bidirectional"))
    )
    (net (code "81") (name "unconnected-(IC2-PCINT24{slash}RXD0_PD0-Pad14)") (class "Default")
      (node (ref "IC2") (pin "14") (pinfunction "PCINT24/RXD0_PD0_14") (pintype "bidirectional"))
    )
    (net (code "82") (name "unconnected-(IC2-PCINT25{slash}TXD0_PD1-Pad15)") (class "Default")
      (node (ref "IC2") (pin "15") (pinfunction "PCINT25/TXD0_PD1_15") (pintype "bidirectional"))
    )
    (net (code "83") (name "unconnected-(IC2-PCINT26{slash}INT0_PD2-Pad16)") (class "Default")
      (node (ref "IC2") (pin "16") (pinfunction "PCINT26/INT0_PD2_16") (pintype "bidirectional"))
    )
    (net (code "84") (name "unconnected-(IC2-PCINT27{slash}INT1_PD3-Pad17)") (class "Default")
      (node (ref "IC2") (pin "17") (pinfunction "PCINT27/INT1_PD3_17") (pintype "bidirectional"))
    )
    (net (code "85") (name "unconnected-(IC3-PCINT23{slash}TOSC2_PC7-Pad29)") (class "Default")
      (node (ref "IC3") (pin "29") (pinfunction "PCINT23/TOSC2_PC7_29") (pintype "bidirectional"))
    )
    (net (code "86") (name "unconnected-(PROG_CON1-Pad3)") (class "Default")
      (node (ref "PROG_CON1") (pin "3") (pinfunction "3_3") (pintype "passive"))
    )
    (net (code "87") (name "unconnected-(U$17-3.3V-Pad3V3)") (class "Default")
      (node (ref "U$17") (pin "3V3") (pinfunction "3.3V_3V3") (pintype "bidirectional"))
    )
    (net (code "88") (name "unconnected-(U$17-I2CADDR-PadADR)") (class "Default")
      (node (ref "U$17") (pin "ADR") (pinfunction "I2CADDR_ADR") (pintype "bidirectional"))
    )
    (net (code "89") (name "unconnected-(U$17-PadINT)") (class "Default")
      (node (ref "U$17") (pin "INT") (pinfunction "INT_INT") (pintype "bidirectional"))
    )
    (net (code "90") (name "unconnected-(U$17-PadPS0)") (class "Default")
      (node (ref "U$17") (pin "PS0") (pinfunction "PS0_PS0") (pintype "bidirectional"))
    )
    (net (code "91") (name "unconnected-(U$17-PadPS1)") (class "Default")
      (node (ref "U$17") (pin "PS1") (pinfunction "PS1_PS1") (pintype "bidirectional"))
    )
    (net (code "92") (name "unconnected-(U$17-PadRST)") (class "Default")
      (node (ref "U$17") (pin "RST") (pinfunction "RST_RST") (pintype "bidirectional"))
    )
    (net (code "93") (name "unconnected-(US_EST-Pad4)") (class "Default")
      (node (ref "US_EST") (pin "4") (pinfunction "4_4") (pintype "passive"))
    )
    (net (code "94") (name "unconnected-(US_NORD-Pad4)") (class "Default")
      (node (ref "US_NORD") (pin "4") (pinfunction "4_4") (pintype "passive"))
    )
    (net (code "95") (name "unconnected-(US_OVEST-Pad4)") (class "Default")
      (node (ref "US_OVEST") (pin "4") (pinfunction "4_4") (pintype "passive"))
    )
    (net (code "96") (name "unconnected-(US_SUD-Pad4)") (class "Default")
      (node (ref "US_SUD") (pin "4") (pinfunction "4_4") (pintype "passive"))
    )
  )
)
